# ioboard.net
KiCad netlist of a schematic drawn in EAGLE
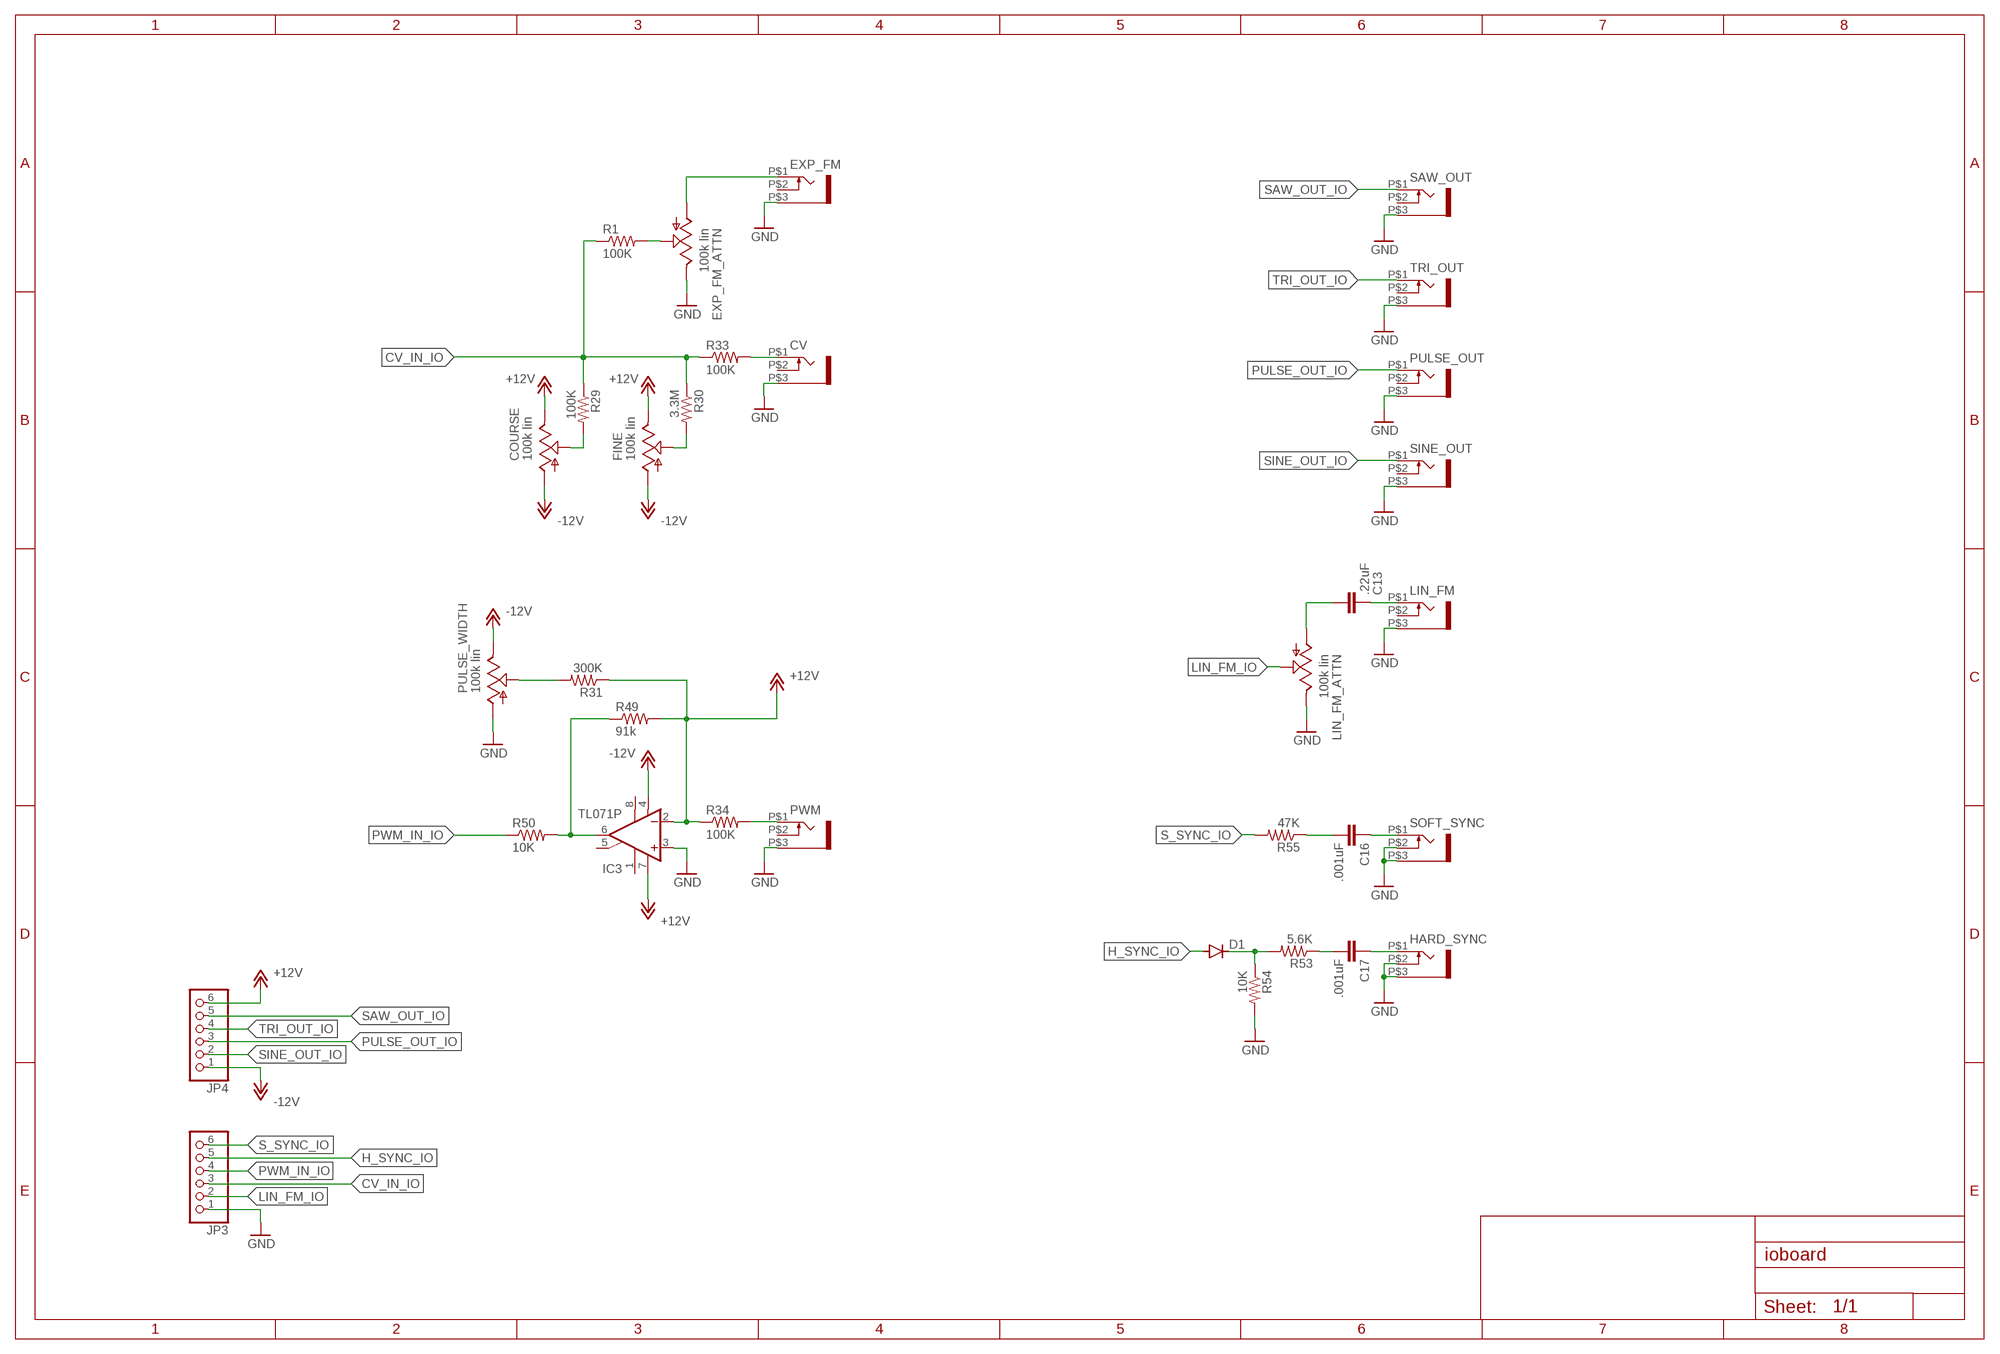
[diagram p0: schematic, sheet 1]

(export (version "E")
  (design (tool "Eeschema 10.0.6"))
  (components
    (comp (ref "C13")
      (value ".22uF")
      (footprint "eagle-import:C050-024X044")
      (libsource (lib "eagle-import") (part "C-EU050-024X044"))
    )
    (comp (ref "C16")
      (value ".001uF")
      (footprint "eagle-import:C050-024X044")
      (libsource (lib "eagle-import") (part "C-EU050-024X044"))
    )
    (comp (ref "C17")
      (value ".001uF")
      (footprint "eagle-import:C050-024X044")
      (libsource (lib "eagle-import") (part "C-EU050-024X044"))
    )
    (comp (ref "COURSE")
      (value "100k lin")
      (footprint "eagle-import:EVUF")
      (libsource (lib "eagle-import") (part "ALPHA-9MMA"))
    )
    (comp (ref "CV")
      (value "WQP-PJ301M-12_JACK")
      (footprint "eagle-import:WQP-PJ301M-12_JACK")
      (libsource (lib "eagle-import") (part "WQP-PJ301M-12_JACK"))
    )
    (comp (ref "D1")
      (value "1N4148DO35-7")
      (footprint "eagle-import:DO35-7")
      (libsource (lib "eagle-import") (part "1N4148DO35-7"))
    )
    (comp (ref "EXP_FM")
      (value "WQP-PJ301M-12_JACK")
      (footprint "eagle-import:WQP-PJ301M-12_JACK")
      (libsource (lib "eagle-import") (part "WQP-PJ301M-12_JACK"))
    )
    (comp (ref "EXP_FM_ATTN")
      (value "100k lin")
      (footprint "eagle-import:EVUF")
      (libsource (lib "eagle-import") (part "ALPHA-9MMA"))
    )
    (comp (ref "FINE")
      (value "100k lin")
      (footprint "eagle-import:EVUF")
      (libsource (lib "eagle-import") (part "ALPHA-9MMA"))
    )
    (comp (ref "HARD_SYNC")
      (value "WQP-PJ301M-12_JACK")
      (footprint "eagle-import:WQP-PJ301M-12_JACK")
      (libsource (lib "eagle-import") (part "WQP-PJ301M-12_JACK"))
    )
    (comp (ref "IC3")
      (value "TL071P")
      (footprint "eagle-import:DIL08")
      (libsource (lib "eagle-import") (part "TL071P"))
    )
    (comp (ref "JP3")
      (value "PINHD-1X6")
      (footprint "eagle-import:1X06")
      (libsource (lib "eagle-import") (part "PINHD-1X6"))
    )
    (comp (ref "JP4")
      (value "PINHD-1X6")
      (footprint "eagle-import:1X06")
      (libsource (lib "eagle-import") (part "PINHD-1X6"))
    )
    (comp (ref "LIN_FM")
      (value "WQP-PJ301M-12_JACK")
      (footprint "eagle-import:WQP-PJ301M-12_JACK")
      (libsource (lib "eagle-import") (part "WQP-PJ301M-12_JACK"))
    )
    (comp (ref "LIN_FM_ATTN")
      (value "100k lin")
      (footprint "eagle-import:EVUF")
      (libsource (lib "eagle-import") (part "ALPHA-9MMA"))
    )
    (comp (ref "PULSE_OUT")
      (value "WQP-PJ301M-12_JACK")
      (footprint "eagle-import:WQP-PJ301M-12_JACK")
      (libsource (lib "eagle-import") (part "WQP-PJ301M-12_JACK"))
    )
    (comp (ref "PULSE_WIDTH")
      (value "100k lin")
      (footprint "eagle-import:EVUF")
      (libsource (lib "eagle-import") (part "ALPHA-9MMA"))
    )
    (comp (ref "PWM")
      (value "WQP-PJ301M-12_JACK")
      (footprint "eagle-import:WQP-PJ301M-12_JACK")
      (libsource (lib "eagle-import") (part "WQP-PJ301M-12_JACK"))
    )
    (comp (ref "R1")
      (value "100K")
      (footprint "eagle-import:0207_7")
      (libsource (lib "eagle-import") (part "R-US_0207/7"))
    )
    (comp (ref "R29")
      (value "100K")
      (footprint "eagle-import:0207_7")
      (libsource (lib "eagle-import") (part "R-US_0207/7"))
    )
    (comp (ref "R30")
      (value "3.3M")
      (footprint "eagle-import:0207_7")
      (libsource (lib "eagle-import") (part "R-US_0207/7"))
    )
    (comp (ref "R31")
      (value "300K")
      (footprint "eagle-import:0207_7")
      (libsource (lib "eagle-import") (part "R-US_0207/7"))
    )
    (comp (ref "R33")
      (value "100K")
      (footprint "eagle-import:0207_7")
      (libsource (lib "eagle-import") (part "R-US_0207/7"))
    )
    (comp (ref "R34")
      (value "100K")
      (footprint "eagle-import:0207_7")
      (libsource (lib "eagle-import") (part "R-US_0207/7"))
    )
    (comp (ref "R49")
      (value "91k")
      (footprint "eagle-import:0207_7")
      (libsource (lib "eagle-import") (part "R-US_0207/7"))
    )
    (comp (ref "R50")
      (value "10K")
      (footprint "eagle-import:0207_7")
      (libsource (lib "eagle-import") (part "R-US_0207/7"))
    )
    (comp (ref "R53")
      (value "5.6K")
      (footprint "eagle-import:0207_7")
      (libsource (lib "eagle-import") (part "R-US_0207/7"))
    )
    (comp (ref "R54")
      (value "10K")
      (footprint "eagle-import:0207_7")
      (libsource (lib "eagle-import") (part "R-US_0207/7"))
    )
    (comp (ref "R55")
      (value "47K")
      (footprint "eagle-import:0207_7")
      (libsource (lib "eagle-import") (part "R-US_0207/7"))
    )
    (comp (ref "SAW_OUT")
      (value "WQP-PJ301M-12_JACK")
      (footprint "eagle-import:WQP-PJ301M-12_JACK")
      (libsource (lib "eagle-import") (part "WQP-PJ301M-12_JACK"))
    )
    (comp (ref "SINE_OUT")
      (value "WQP-PJ301M-12_JACK")
      (footprint "eagle-import:WQP-PJ301M-12_JACK")
      (libsource (lib "eagle-import") (part "WQP-PJ301M-12_JACK"))
    )
    (comp (ref "SOFT_SYNC")
      (value "WQP-PJ301M-12_JACK")
      (footprint "eagle-import:WQP-PJ301M-12_JACK")
      (libsource (lib "eagle-import") (part "WQP-PJ301M-12_JACK"))
    )
    (comp (ref "TRI_OUT")
      (value "WQP-PJ301M-12_JACK")
      (footprint "eagle-import:WQP-PJ301M-12_JACK")
      (libsource (lib "eagle-import") (part "WQP-PJ301M-12_JACK"))
    )
  )
  (nets
    (net (code "1") (name "+12V") (class "Default")
      (node (ref "COURSE") (pin "3") (pinfunction "E_3") (pintype "passive"))
      (node (ref "FINE") (pin "3") (pinfunction "E_3") (pintype "passive"))
      (node (ref "IC3") (pin "2") (pinfunction "-IN_2") (pintype "input"))
      (node (ref "IC3") (pin "7") (pinfunction "V+_7") (pintype "power_in"))
      (node (ref "JP4") (pin "6") (pinfunction "6_6") (pintype "passive"))
      (node (ref "R31") (pin "1") (pinfunction "1_1") (pintype "passive"))
      (node (ref "R34") (pin "1") (pinfunction "1_1") (pintype "passive"))
      (node (ref "R49") (pin "2") (pinfunction "2_2") (pintype "passive"))
    )
    (net (code "2") (name "-12V") (class "Default")
      (node (ref "COURSE") (pin "1") (pinfunction "A_1") (pintype "passive"))
      (node (ref "FINE") (pin "1") (pinfunction "A_1") (pintype "passive"))
      (node (ref "IC3") (pin "4") (pinfunction "V-_4") (pintype "power_in"))
      (node (ref "JP4") (pin "1") (pinfunction "1_1") (pintype "passive"))
      (node (ref "PULSE_WIDTH") (pin "3") (pinfunction "E_3") (pintype "passive"))
    )
    (net (code "3") (name "CV_IN_IO") (class "Default")
      (node (ref "JP3") (pin "3") (pinfunction "3_3") (pintype "passive"))
      (node (ref "R1") (pin "1") (pinfunction "1_1") (pintype "passive"))
      (node (ref "R29") (pin "1") (pinfunction "1_1") (pintype "passive"))
      (node (ref "R30") (pin "1") (pinfunction "1_1") (pintype "passive"))
      (node (ref "R33") (pin "1") (pinfunction "1_1") (pintype "passive"))
    )
    (net (code "4") (name "GND") (class "Default")
      (node (ref "CV") (pin "P$3") (pinfunction "1_P$3") (pintype "passive"))
      (node (ref "EXP_FM") (pin "P$3") (pinfunction "1_P$3") (pintype "passive"))
      (node (ref "EXP_FM_ATTN") (pin "3") (pinfunction "E_3") (pintype "passive"))
      (node (ref "HARD_SYNC") (pin "P$2") (pinfunction "3_P$2") (pintype "passive"))
      (node (ref "HARD_SYNC") (pin "P$3") (pinfunction "1_P$3") (pintype "passive"))
      (node (ref "IC3") (pin "3") (pinfunction "+IN_3") (pintype "input"))
      (node (ref "JP3") (pin "1") (pinfunction "1_1") (pintype "passive"))
      (node (ref "LIN_FM") (pin "P$3") (pinfunction "1_P$3") (pintype "passive"))
      (node (ref "LIN_FM_ATTN") (pin "3") (pinfunction "E_3") (pintype "passive"))
      (node (ref "PULSE_OUT") (pin "P$3") (pinfunction "1_P$3") (pintype "passive"))
      (node (ref "PULSE_WIDTH") (pin "1") (pinfunction "A_1") (pintype "passive"))
      (node (ref "PWM") (pin "P$3") (pinfunction "1_P$3") (pintype "passive"))
      (node (ref "R54") (pin "2") (pinfunction "2_2") (pintype "passive"))
      (node (ref "SAW_OUT") (pin "P$3") (pinfunction "1_P$3") (pintype "passive"))
      (node (ref "SINE_OUT") (pin "P$3") (pinfunction "1_P$3") (pintype "passive"))
      (node (ref "SOFT_SYNC") (pin "P$2") (pinfunction "3_P$2") (pintype "passive"))
      (node (ref "SOFT_SYNC") (pin "P$3") (pinfunction "1_P$3") (pintype "passive"))
      (node (ref "TRI_OUT") (pin "P$3") (pinfunction "1_P$3") (pintype "passive"))
    )
    (net (code "5") (name "H_SYNC_IO") (class "Default")
      (node (ref "D1") (pin "A") (pinfunction "A_A") (pintype "passive"))
      (node (ref "JP3") (pin "5") (pinfunction "5_5") (pintype "passive"))
    )
    (net (code "6") (name "LIN_FM_IO") (class "Default")
      (node (ref "EXP_FM_ATTN") (pin "2") (pinfunction "S_2") (pintype "passive"))
      (node (ref "JP3") (pin "2") (pinfunction "2_2") (pintype "passive"))
      (node (ref "LIN_FM_ATTN") (pin "2") (pinfunction "S_2") (pintype "passive"))
      (node (ref "R1") (pin "2") (pinfunction "2_2") (pintype "passive"))
    )
    (net (code "7") (name "Net-(C16-Pad2)") (class "Default")
      (node (ref "C16") (pin "2") (pinfunction "2_2") (pintype "passive"))
      (node (ref "R55") (pin "1") (pinfunction "1_1") (pintype "passive"))
    )
    (net (code "8") (name "Net-(C17-Pad2)") (class "Default")
      (node (ref "C17") (pin "2") (pinfunction "2_2") (pintype "passive"))
      (node (ref "R53") (pin "1") (pinfunction "1_1") (pintype "passive"))
    )
    (net (code "9") (name "Net-(COURSE-S)") (class "Default")
      (node (ref "COURSE") (pin "2") (pinfunction "S_2") (pintype "passive"))
      (node (ref "R29") (pin "2") (pinfunction "2_2") (pintype "passive"))
    )
    (net (code "10") (name "Net-(CV-2)") (class "Default")
      (node (ref "CV") (pin "P$1") (pinfunction "2_P$1") (pintype "passive"))
      (node (ref "R33") (pin "2") (pinfunction "2_2") (pintype "passive"))
    )
    (net (code "11") (name "Net-(D1-PadC)") (class "Default")
      (node (ref "D1") (pin "C") (pinfunction "C_C") (pintype "passive"))
      (node (ref "R53") (pin "2") (pinfunction "2_2") (pintype "passive"))
      (node (ref "R54") (pin "1") (pinfunction "1_1") (pintype "passive"))
    )
    (net (code "12") (name "Net-(EXP_FM-2)") (class "Default")
      (node (ref "EXP_FM") (pin "P$1") (pinfunction "2_P$1") (pintype "passive"))
      (node (ref "EXP_FM_ATTN") (pin "1") (pinfunction "A_1") (pintype "passive"))
    )
    (net (code "13") (name "Net-(FINE-S)") (class "Default")
      (node (ref "FINE") (pin "2") (pinfunction "S_2") (pintype "passive"))
      (node (ref "R30") (pin "2") (pinfunction "2_2") (pintype "passive"))
    )
    (net (code "14") (name "Net-(HARD_SYNC-2)") (class "Default")
      (node (ref "C17") (pin "1") (pinfunction "1_1") (pintype "passive"))
      (node (ref "HARD_SYNC") (pin "P$1") (pinfunction "2_P$1") (pintype "passive"))
    )
    (net (code "15") (name "Net-(IC3-OUT)") (class "Default")
      (node (ref "IC3") (pin "6") (pinfunction "OUT_6") (pintype "output"))
      (node (ref "R49") (pin "1") (pinfunction "1_1") (pintype "passive"))
      (node (ref "R50") (pin "2") (pinfunction "2_2") (pintype "passive"))
    )
    (net (code "16") (name "Net-(LIN_FM-2)") (class "Default")
      (node (ref "C13") (pin "2") (pinfunction "2_2") (pintype "passive"))
      (node (ref "LIN_FM") (pin "P$1") (pinfunction "2_P$1") (pintype "passive"))
    )
    (net (code "17") (name "Net-(LIN_FM_ATTN-A)") (class "Default")
      (node (ref "C13") (pin "1") (pinfunction "1_1") (pintype "passive"))
      (node (ref "LIN_FM_ATTN") (pin "1") (pinfunction "A_1") (pintype "passive"))
    )
    (net (code "18") (name "Net-(PULSE_WIDTH-S)") (class "Default")
      (node (ref "PULSE_WIDTH") (pin "2") (pinfunction "S_2") (pintype "passive"))
      (node (ref "R31") (pin "2") (pinfunction "2_2") (pintype "passive"))
    )
    (net (code "19") (name "Net-(PWM-2)") (class "Default")
      (node (ref "PWM") (pin "P$1") (pinfunction "2_P$1") (pintype "passive"))
      (node (ref "R34") (pin "2") (pinfunction "2_2") (pintype "passive"))
    )
    (net (code "20") (name "Net-(SOFT_SYNC-2)") (class "Default")
      (node (ref "C16") (pin "1") (pinfunction "1_1") (pintype "passive"))
      (node (ref "SOFT_SYNC") (pin "P$1") (pinfunction "2_P$1") (pintype "passive"))
    )
    (net (code "21") (name "PULSE_OUT_IO") (class "Default")
      (node (ref "JP4") (pin "3") (pinfunction "3_3") (pintype "passive"))
      (node (ref "PULSE_OUT") (pin "P$1") (pinfunction "2_P$1") (pintype "passive"))
    )
    (net (code "22") (name "PWM_IN_IO") (class "Default")
      (node (ref "JP3") (pin "4") (pinfunction "4_4") (pintype "passive"))
      (node (ref "R50") (pin "1") (pinfunction "1_1") (pintype "passive"))
    )
    (net (code "23") (name "SAW_OUT_IO") (class "Default")
      (node (ref "JP4") (pin "5") (pinfunction "5_5") (pintype "passive"))
      (node (ref "SAW_OUT") (pin "P$1") (pinfunction "2_P$1") (pintype "passive"))
    )
    (net (code "24") (name "SINE_OUT_IO") (class "Default")
      (node (ref "JP4") (pin "2") (pinfunction "2_2") (pintype "passive"))
      (node (ref "SINE_OUT") (pin "P$1") (pinfunction "2_P$1") (pintype "passive"))
    )
    (net (code "25") (name "S_SYNC_IO") (class "Default")
      (node (ref "JP3") (pin "6") (pinfunction "6_6") (pintype "passive"))
      (node (ref "R55") (pin "2") (pinfunction "2_2") (pintype "passive"))
    )
    (net (code "26") (name "TRI_OUT_IO") (class "Default")
      (node (ref "JP4") (pin "4") (pinfunction "4_4") (pintype "passive"))
      (node (ref "TRI_OUT") (pin "P$1") (pinfunction "2_P$1") (pintype "passive"))
    )
    (net (code "27") (name "unconnected-(CV-3-PadP$2)") (class "Default")
      (node (ref "CV") (pin "P$2") (pinfunction "3_P$2") (pintype "passive"))
    )
    (net (code "28") (name "unconnected-(EXP_FM-3-PadP$2)") (class "Default")
      (node (ref "EXP_FM") (pin "P$2") (pinfunction "3_P$2") (pintype "passive"))
    )
    (net (code "29") (name "unconnected-(IC3-ON1-Pad1)") (class "Default")
      (node (ref "IC3") (pin "1") (pinfunction "ON1_1") (pintype "passive"))
    )
    (net (code "30") (name "unconnected-(IC3-ON2-Pad5)") (class "Default")
      (node (ref "IC3") (pin "5") (pinfunction "ON2_5") (pintype "passive"))
    )
    (net (code "31") (name "unconnected-(IC3-OPT-Pad8)") (class "Default")
      (node (ref "IC3") (pin "8") (pinfunction "OPT_8") (pintype "passive"))
    )
    (net (code "32") (name "unconnected-(LIN_FM-3-PadP$2)") (class "Default")
      (node (ref "LIN_FM") (pin "P$2") (pinfunction "3_P$2") (pintype "passive"))
    )
    (net (code "33") (name "unconnected-(PULSE_OUT-3-PadP$2)") (class "Default")
      (node (ref "PULSE_OUT") (pin "P$2") (pinfunction "3_P$2") (pintype "passive"))
    )
    (net (code "34") (name "unconnected-(PWM-3-PadP$2)") (class "Default")
      (node (ref "PWM") (pin "P$2") (pinfunction "3_P$2") (pintype "passive"))
    )
    (net (code "35") (name "unconnected-(SAW_OUT-3-PadP$2)") (class "Default")
      (node (ref "SAW_OUT") (pin "P$2") (pinfunction "3_P$2") (pintype "passive"))
    )
    (net (code "36") (name "unconnected-(SINE_OUT-3-PadP$2)") (class "Default")
      (node (ref "SINE_OUT") (pin "P$2") (pinfunction "3_P$2") (pintype "passive"))
    )
    (net (code "37") (name "unconnected-(TRI_OUT-3-PadP$2)") (class "Default")
      (node (ref "TRI_OUT") (pin "P$2") (pinfunction "3_P$2") (pintype "passive"))
    )
  )
)
